# MainSheet.net
KiCad netlist of a schematic drawn in Altium Designer
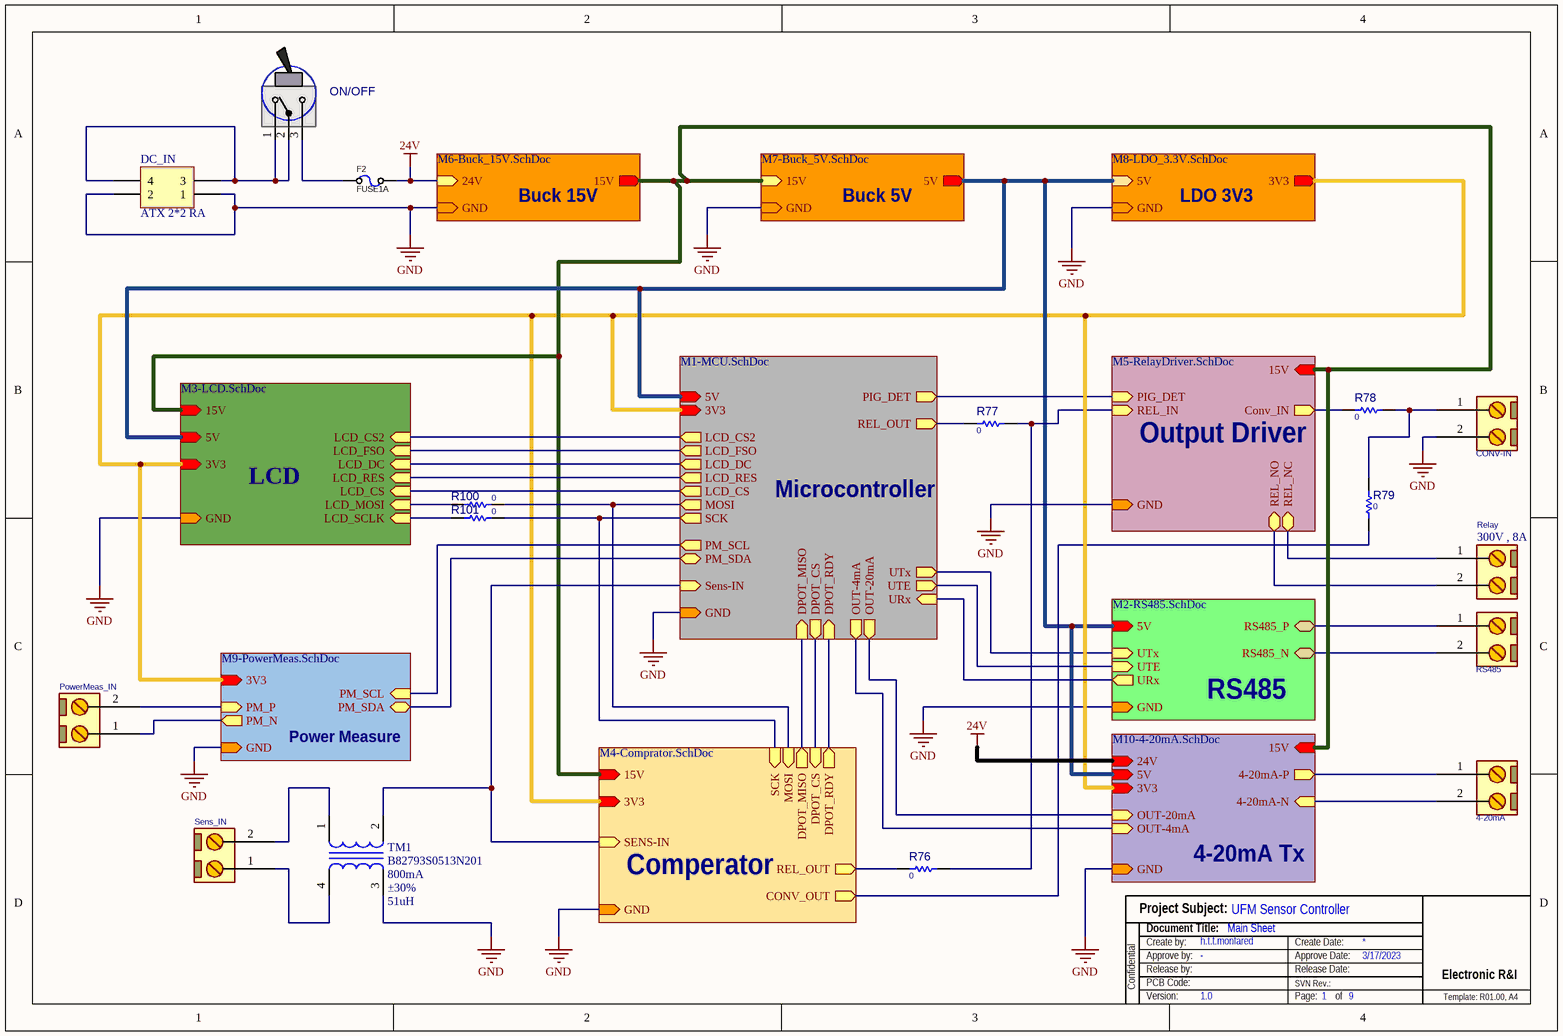
[diagram p0: MainSheet.SchDoc]

(export (version "E")
  (design (tool "Eeschema 10.0.6"))
  (components
    (comp (ref "4-20mA")
      (value "Output")
      (footprint "MSTB_2")
      (description "CONN, PHOENIX MSTB, 5-G, 5.08mm pitch")
      (libsource (lib "conn_power_terminalB") (part "CONN_MSTB_2"))
    )
    (comp (ref "CONV-IN")
      (value "Output")
      (footprint "MSTB_2")
      (description "CONN, PHOENIX MSTB, 5-G, 5.08mm pitch")
      (libsource (lib "conn_power_terminalB") (part "CONN_MSTB_2"))
    )
    (comp (ref "DC_IN")
      (value "ATX 2*2 RA")
      (footprint "Crouse-Draft:POWER_2X2-RA")
      (description "Header, 2-Pin, Dual row")
      (fields (field (name "PUBLISHER") "Altium Limited"))
      (libsource (lib "Schematic") (part "Header 2X2"))
    )
    (comp (ref "F2")
      (value "FUSE1A")
      (footprint "F2410")
      (description "Fuse, 1A, 125VDC, 2410, SMD, Fast Acting")
      (fields (field (name "MANF") "Reomax") (field (name "MANF_P#") "SFE1100"))
      (libsource (lib "protect_tvs_esd_fuse") (part "FUSE_1A_2410"))
    )
    (comp (ref "ON/OFF")
      (value "ToggleSwitch")
      (footprint "SWTOG_SPDT_R_M2012")
      (description "SWITCH, TOGGLE, SPDT, THD")
      (fields (field (name "MANF") "NKK") (field (name "MANF_PART#") "M2012SA2W30"))
      (libsource (lib "switch_toggle") (part "SWTOG_SPDT_R_M2012"))
    )
    (comp (ref "PowerMeas_IN")
      (value "~")
      (footprint "MSTB_2")
      (description "CONN, PHOENIX MSTB, 5-G, 5.08mm pitch")
      (libsource (lib "") (part "CONN_MSTB_2_1"))
    )
    (comp (ref "R76")
      (value "0")
      (footprint "R1206")
      (description "RESISTOR, SMD")
      (libsource (lib "passive_smd") (part "RES_SMD"))
    )
    (comp (ref "R77")
      (value "0")
      (footprint "R1206")
      (description "RESISTOR, SMD")
      (libsource (lib "passive_smd") (part "RES_SMD"))
    )
    (comp (ref "R78")
      (value "0")
      (footprint "R1206")
      (description "RESISTOR, SMD")
      (libsource (lib "passive_smd") (part "RES_SMD"))
    )
    (comp (ref "R79")
      (value "0")
      (footprint "R1206")
      (description "RESISTOR, SMD")
      (libsource (lib "passive_smd") (part "RES_SMD"))
    )
    (comp (ref "R100")
      (value "0")
      (footprint "R1206")
      (description "RESISTOR, SMD")
      (libsource (lib "passive_smd") (part "RES_SMD"))
    )
    (comp (ref "R101")
      (value "0")
      (footprint "R1206")
      (description "RESISTOR, SMD")
      (libsource (lib "passive_smd") (part "RES_SMD"))
    )
    (comp (ref "Relay")
      (value "300V , 8A")
      (footprint "MSTB_2")
      (description "CONN, PHOENIX MSTB, 5-G, 5.08mm pitch")
      (libsource (lib "conn_power_terminalB") (part "CONN_MSTB_2"))
    )
    (comp (ref "RS485")
      (value "Output")
      (footprint "MSTB_2")
      (description "CONN, PHOENIX MSTB, 5-G, 5.08mm pitch")
      (libsource (lib "conn_power_terminalB") (part "CONN_MSTB_2"))
    )
    (comp (ref "Sens_IN")
      (value "~")
      (footprint "MSTB_2")
      (description "CONN, PHOENIX MSTB, 5-G, 5.08mm pitch")
      (libsource (lib "") (part "CONN_MSTB_2_1"))
    )
    (comp (ref "TM1")
      (value "B82793S0513N201")
      (footprint "Choke-7.1_6.0_4.8:Choke-7.1_6.0_4.8")
      (description "Inductor,S,Choke,Ferrite,800mA,30%,7.1x6x4.8mm")
      (fields
        (field (name "CURRENT-RATED") "800mA")
        (field (name "TOLERANCE") "±30%")
        (field (name "ALTIUM_VALUE") "51uH")
      )
      (libsource (lib "Crouse") (part "Choke"))
    )
  )
  (nets
    (net (code "2") (name "/4-20mA-N") (class "Default")
      (node (ref "4-20mA") (pin "2") (pinfunction "2_2") (pintype "passive"))
    )
    (net (code "3") (name "/4-20mA-P") (class "Default")
      (node (ref "4-20mA") (pin "1") (pinfunction "1_1") (pintype "passive"))
    )
    (net (code "6") (name "/CONV_OUT") (class "Default")
      (node (ref "R79") (pin "1") (pinfunction "1_1") (pintype "passive"))
    )
    (net (code "7") (name "/Conv_IN") (class "Default")
      (node (ref "R78") (pin "1") (pinfunction "1_1") (pintype "passive"))
    )
    (net (code "15") (name "/LCD_MOSI") (class "Default")
      (node (ref "R100") (pin "1") (pinfunction "1_1") (pintype "passive"))
    )
    (net (code "17") (name "/LCD_SCLK") (class "Default")
      (node (ref "R101") (pin "1") (pinfunction "1_1") (pintype "passive"))
    )
    (net (code "18") (name "/MOSI") (class "Default")
      (node (ref "R100") (pin "2") (pinfunction "2_2") (pintype "passive"))
    )
    (net (code "22") (name "/PM_N") (class "Default")
      (node (ref "PowerMeas_IN") (pin "1") (pinfunction "1_1") (pintype "passive"))
    )
    (net (code "23") (name "/PM_P") (class "Default")
      (node (ref "PowerMeas_IN") (pin "2") (pinfunction "2_2") (pintype "passive"))
    )
    (net (code "26") (name "/REL_IN") (class "Default")
      (node (ref "R76") (pin "2") (pinfunction "2_2") (pintype "passive"))
      (node (ref "R77") (pin "2") (pinfunction "2_2") (pintype "passive"))
    )
    (net (code "27") (name "/REL_NC") (class "Default")
      (node (ref "Relay") (pin "1") (pinfunction "1_1") (pintype "passive"))
    )
    (net (code "28") (name "/REL_NO") (class "Default")
      (node (ref "Relay") (pin "2") (pinfunction "2_2") (pintype "passive"))
    )
    (net (code "29") (name "/REL_OUT") (class "Default")
      (node (ref "R76") (pin "1") (pinfunction "1_1") (pintype "passive"))
    )
    (net (code "30") (name "/REL_OUT_1") (class "Default")
      (node (ref "R77") (pin "1") (pinfunction "1_1") (pintype "passive"))
    )
    (net (code "31") (name "/RS485_N") (class "Default")
      (node (ref "RS485") (pin "2") (pinfunction "2_2") (pintype "passive"))
    )
    (net (code "32") (name "/RS485_P") (class "Default")
      (node (ref "RS485") (pin "1") (pinfunction "1_1") (pintype "passive"))
    )
    (net (code "33") (name "/SCK") (class "Default")
      (node (ref "R101") (pin "2") (pinfunction "2_2") (pintype "passive"))
    )
    (net (code "34") (name "/SENS-IN") (class "Default")
      (node (ref "TM1") (pin "2") (pinfunction "2_2") (pintype "passive"))
    )
    (net (code "38") (name "24V") (class "Default")
      (node (ref "F2") (pin "2") (pinfunction "2_2") (pintype "passive"))
    )
    (net (code "39") (name "GND") (class "Default")
      (node (ref "CONV-IN") (pin "2") (pinfunction "2_2") (pintype "passive"))
      (node (ref "DC_IN") (pin "1") (pinfunction "1_1") (pintype "passive"))
      (node (ref "DC_IN") (pin "2") (pinfunction "2_2") (pintype "passive"))
      (node (ref "TM1") (pin "3") (pinfunction "3_3") (pintype "passive"))
    )
    (net (code "40") (name "Net-(CONV-IN-Pad1)") (class "Default")
      (node (ref "CONV-IN") (pin "1") (pinfunction "1_1") (pintype "passive"))
      (node (ref "R78") (pin "2") (pinfunction "2_2") (pintype "passive"))
      (node (ref "R79") (pin "2") (pinfunction "2_2") (pintype "passive"))
    )
    (net (code "41") (name "Net-(ON/OFF-COM)") (class "Default")
      (node (ref "DC_IN") (pin "3") (pinfunction "3_3") (pintype "passive"))
      (node (ref "DC_IN") (pin "4") (pinfunction "4_4") (pintype "passive"))
      (node (ref "ON/OFF") (pin "1") (pinfunction "T1_1") (pintype "passive"))
      (node (ref "ON/OFF") (pin "2") (pinfunction "COM_2") (pintype "passive"))
    )
    (net (code "42") (name "Net-(ON/OFF-T2)") (class "Default")
      (node (ref "F2") (pin "1") (pinfunction "1_1") (pintype "passive"))
      (node (ref "ON/OFF") (pin "3") (pinfunction "T2_3") (pintype "passive"))
    )
    (net (code "43") (name "Net-(Sens_IN-Pad1)") (class "Default")
      (node (ref "Sens_IN") (pin "1") (pinfunction "1_1") (pintype "passive"))
      (node (ref "TM1") (pin "4") (pinfunction "4_4") (pintype "passive"))
    )
    (net (code "44") (name "Net-(Sens_IN-Pad2)") (class "Default")
      (node (ref "Sens_IN") (pin "2") (pinfunction "2_2") (pintype "passive"))
      (node (ref "TM1") (pin "1") (pinfunction "1_1") (pintype "passive"))
    )
  )
)
